# RMII_Ethernet.net
KiCad netlist of a schematic drawn in Altium Designer
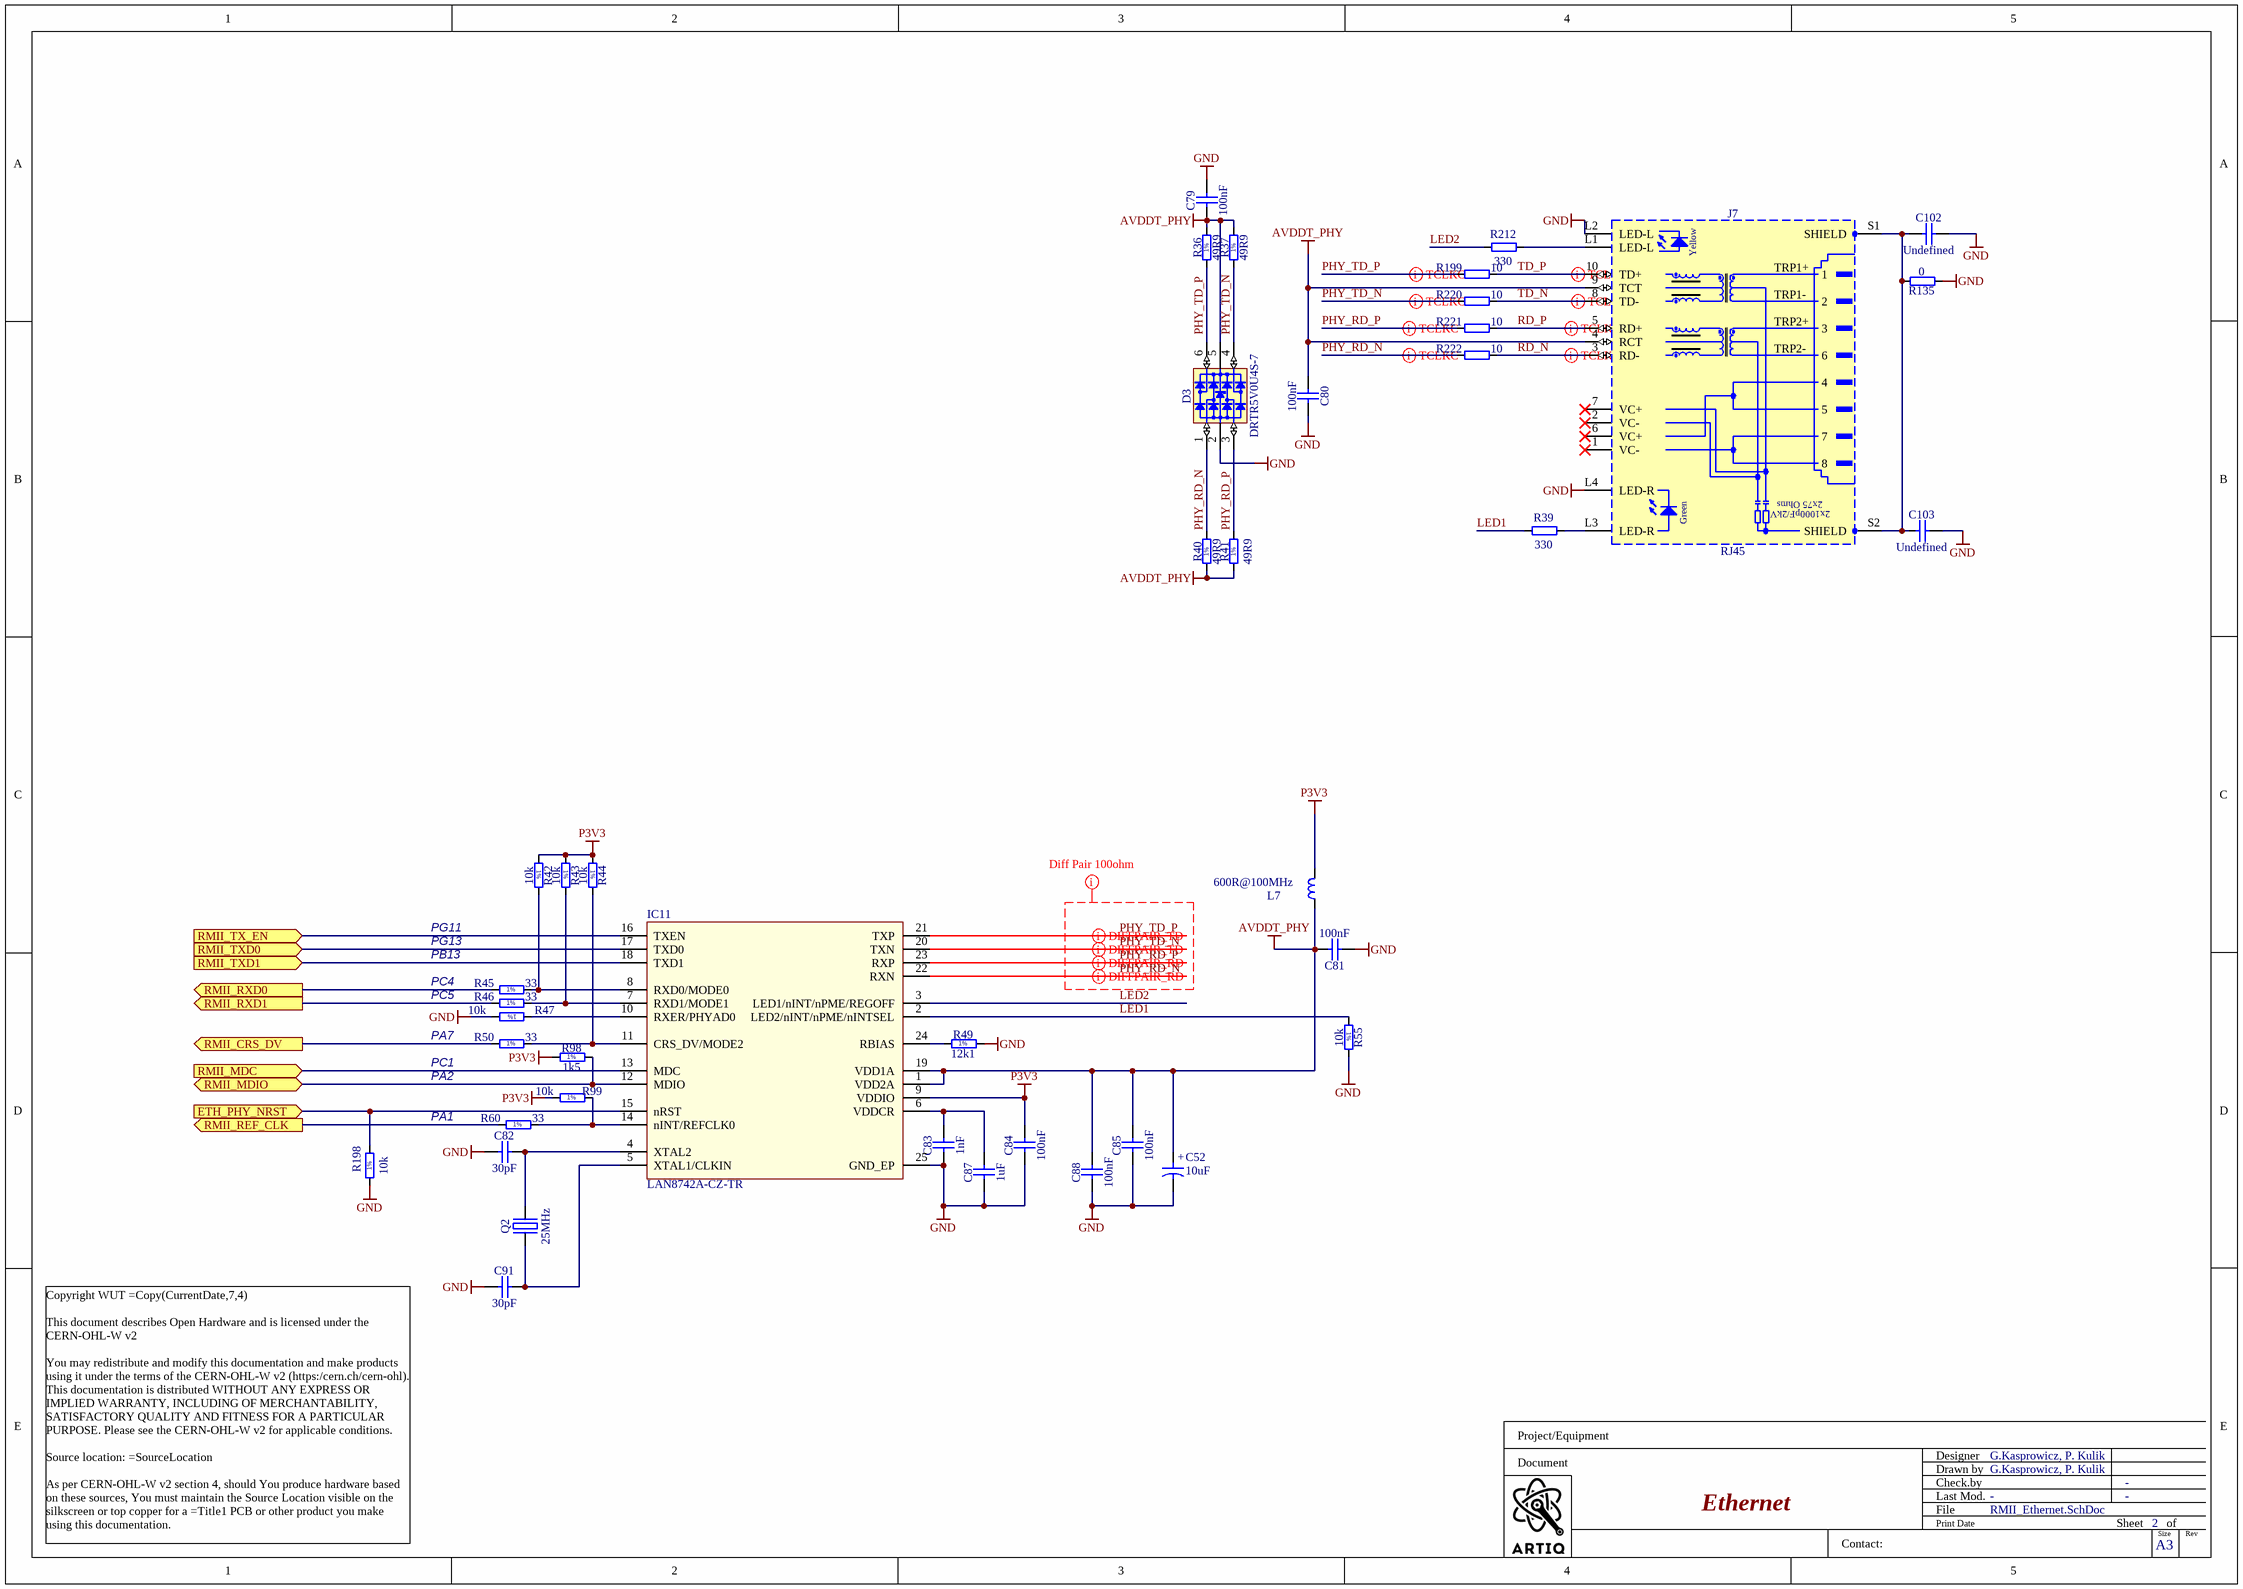
[diagram p0: RMII_Ethernet.SchDoc]

(export (version "E")
  (design (tool "Eeschema 10.0.6"))
  (components
    (comp (ref "C52")
      (value "10uF")
      (footprint "CAPMP3216X180N")
      (description "Polarised capacitor")
      (fields
        (field (name "PART NUMBER") "CTE3216-18_10UF_16V_20%_AVX_TCJ")
        (field (name "VOLTAGE") "16V")
        (field (name "AUTHOR") "CERN DEM JLC")
      )
      (libsource (lib "Capacitors") (part "Capacitor - polarized"))
    )
    (comp (ref "C79")
      (value "100nF")
      (footprint "CAPC1005X55N")
      (description "Non-polarised capacitor")
      (fields
        (field (name "PART NUMBER") "CC0402_100NF_16V_10%_X5R")
        (field (name "VOLTAGE") "16V")
        (field (name "AUTHOR") "CERN DEM JLC")
      )
      (libsource (lib "Capacitors") (part "Capacitor - non polarized"))
    )
    (comp (ref "C80")
      (value "100nF")
      (footprint "CAPC1005X55N")
      (description "Non-polarised capacitor")
      (fields
        (field (name "PART NUMBER") "CC0402_100NF_16V_10%_X5R")
        (field (name "VOLTAGE") "16V")
        (field (name "AUTHOR") "CERN DEM JLC")
      )
      (libsource (lib "Capacitors") (part "Capacitor - non polarized"))
    )
    (comp (ref "C81")
      (value "100nF")
      (footprint "CAPC1005X55N")
      (description "Non-polarised capacitor")
      (fields
        (field (name "PART NUMBER") "CC0402_100NF_16V_10%_X5R")
        (field (name "VOLTAGE") "16V")
        (field (name "AUTHOR") "CERN DEM JLC")
      )
      (libsource (lib "Capacitors") (part "Capacitor - non polarized"))
    )
    (comp (ref "C82")
      (value "30pF")
      (footprint "CAPC1005X55N")
      (description "Non-polarised capacitor")
      (fields
        (field (name "PART NUMBER") "CC0402_30PF_50V_1%_C0G_MURATA_GJM1555C1H300FB01")
        (field (name "VOLTAGE") "50V")
        (field (name "AUTHOR") "CERN DEM BC")
      )
      (libsource (lib "Capacitors") (part "Capacitor - non polarized"))
    )
    (comp (ref "C83")
      (value "1nF")
      (footprint "CAPC1005X55N")
      (description "Non-polarised capacitor")
      (fields
        (field (name "PART NUMBER") "CC0402_1NF_50V_10%_X7R")
        (field (name "VOLTAGE") "50V")
        (field (name "AUTHOR") "CERN DEM JLC")
      )
      (libsource (lib "Capacitors") (part "Capacitor - non polarized"))
    )
    (comp (ref "C84")
      (value "100nF")
      (footprint "CAPC1005X55N")
      (description "Non-polarised capacitor")
      (fields
        (field (name "PART NUMBER") "CC0402_100NF_16V_10%_X5R")
        (field (name "VOLTAGE") "16V")
        (field (name "AUTHOR") "CERN DEM JLC")
      )
      (libsource (lib "Capacitors") (part "Capacitor - non polarized"))
    )
    (comp (ref "C85")
      (value "100nF")
      (footprint "CAPC1005X55N")
      (description "Non-polarised capacitor")
      (fields
        (field (name "PART NUMBER") "CC0402_100NF_16V_10%_X5R")
        (field (name "VOLTAGE") "16V")
        (field (name "AUTHOR") "CERN DEM JLC")
      )
      (libsource (lib "Capacitors") (part "Capacitor - non polarized"))
    )
    (comp (ref "C87")
      (value "1uF")
      (footprint "CAPC1608X87N")
      (description "Non-polarised capacitor")
      (fields
        (field (name "PART NUMBER") "CC0603_1UF_16V_10%_X7R")
        (field (name "VOLTAGE") "16V")
        (field (name "AUTHOR") "CERN DEM JLC")
      )
      (libsource (lib "Capacitors") (part "Capacitor - non polarized"))
    )
    (comp (ref "C88")
      (value "100nF")
      (footprint "CAPC1005X55N")
      (description "Non-polarised capacitor")
      (fields
        (field (name "PART NUMBER") "CC0402_100NF_16V_10%_X5R")
        (field (name "VOLTAGE") "16V")
        (field (name "AUTHOR") "CERN DEM JLC")
      )
      (libsource (lib "Capacitors") (part "Capacitor - non polarized"))
    )
    (comp (ref "C91")
      (value "30pF")
      (footprint "CAPC1005X55N")
      (description "Non-polarised capacitor")
      (fields
        (field (name "PART NUMBER") "CC0402_30PF_50V_1%_C0G_MURATA_GJM1555C1H300FB01")
        (field (name "VOLTAGE") "50V")
        (field (name "AUTHOR") "CERN DEM BC")
      )
      (libsource (lib "Capacitors") (part "Capacitor - non polarized"))
    )
    (comp (ref "C102")
      (value "Undefined")
      (footprint "CAPC2012X135N")
      (description "Non-polarised capacitor")
      (fields (field (name "PART NUMBER") "CC0805_NO-VALUE") (field (name "AUTHOR") "CERN DEM JLC"))
      (libsource (lib "Capacitors") (part "Capacitor - non polarized"))
    )
    (comp (ref "C103")
      (value "Undefined")
      (footprint "CAPC2012X135N")
      (description "Non-polarised capacitor")
      (fields (field (name "PART NUMBER") "CC0805_NO-VALUE") (field (name "AUTHOR") "CERN DEM JLC"))
      (libsource (lib "Capacitors") (part "Capacitor - non polarized"))
    )
    (comp (ref "D3")
      (value "DRTR5V0U4S-7")
      (footprint "SOT65P210X110-6N")
      (description "Integrated Quad Ultra-Low Capacitance ESD Protection")
      (fields (field (name "MANUFACTURER") "DIODES") (field (name "AUTHOR") "GK"))
      (libsource (lib "Diodes") (part "D_TVS_DRTR5V0U4S-7"))
    )
    (comp (ref "IC11")
      (value "LAN8742A-CZ-TR")
      (footprint "QFN24_0R5_4X4")
      (fields (field (name "MANUFACTURER") "MICROCHIP"))
      (libsource (lib "LIBRARY_SCH") (part "IFC_LAN8742A"))
    )
    (comp (ref "J7")
      (value "RJ45")
      (footprint "ABRACON_ARJM11C7-114-BA-EW2")
      (description "MagJack 10/100BaseT, PoE+, 1X1, OG/Y, -40 to 85*C, Tab Up, RoHS")
      (fields
        (field (name "PART NUMBER") "ARJM11C7-114-BA-EW2")
        (field (name "MANUFACTURER") "Abracon")
        (field (name "AUTHOR") "GK")
      )
      (libsource (lib "LIBRARY_SCH") (part "CON_ETH_POE_ARJM11C7"))
    )
    (comp (ref "L7")
      (value "600R@100MHz")
      (footprint "INDC1005X55N")
      (description "Inductor")
      (fields
        (field (name "PART NUMBER") "IND0402_MURATA_BLM15HD601SN1")
        (field (name "POWER") "300mA")
        (field (name "AUTHOR") "CERN DEM JLC")
      )
      (libsource (lib "Inductors & Transformers") (part "Inductor"))
    )
    (comp (ref "Q2")
      (value "25MHz")
      (footprint "XTAL_ABRACON_ABLS")
      (description "Quartz Crystal")
      (fields
        (field (name "PART NUMBER") "XTAL_25MHZ_ABRACON_ABLS-25.000MHZ-B2F-T")
        (field (name "MANUFACTURER") "ABRACON")
        (field (name "AUTHOR") "CERN DEM JLC")
      )
      (libsource (lib "ICs And Semiconductors") (part "Quartz Crystal"))
    )
    (comp (ref "R36")
      (value "49R9")
      (footprint "RESC1005X40N")
      (description "Resistor - 1%")
      (fields
        (field (name "PART NUMBER") "R0402_49R9_1%_0.0625W_100PPM")
        (field (name "POWER") "0.0625W")
        (field (name "AUTHOR") "CERN DEM JLC")
      )
      (libsource (lib "Resistors") (part "Resistor - 1%"))
    )
    (comp (ref "R37")
      (value "49R9")
      (footprint "RESC1005X40N")
      (description "Resistor - 1%")
      (fields
        (field (name "PART NUMBER") "R0402_49R9_1%_0.0625W_100PPM")
        (field (name "POWER") "0.0625W")
        (field (name "AUTHOR") "CERN DEM JLC")
      )
      (libsource (lib "Resistors") (part "Resistor - 1%"))
    )
    (comp (ref "R39")
      (value "330")
      (footprint "RESC1005X40N")
      (description "Resistor - 1%")
      (fields
        (field (name "PART NUMBER") "R0402_330R_1%_0.0625W_100PPM")
        (field (name "POWER") "0.0625W")
        (field (name "AUTHOR") "CERN DEM JLC")
      )
      (libsource (lib "Resistors") (part "Resistor - 1%"))
    )
    (comp (ref "R40")
      (value "49R9")
      (footprint "RESC1005X40N")
      (description "Resistor - 1%")
      (fields
        (field (name "PART NUMBER") "R0402_49R9_1%_0.0625W_100PPM")
        (field (name "POWER") "0.0625W")
        (field (name "AUTHOR") "CERN DEM JLC")
      )
      (libsource (lib "Resistors") (part "Resistor - 1%"))
    )
    (comp (ref "R41")
      (value "49R9")
      (footprint "RESC1005X40N")
      (description "Resistor - 1%")
      (fields
        (field (name "PART NUMBER") "R0402_49R9_1%_0.0625W_100PPM")
        (field (name "POWER") "0.0625W")
        (field (name "AUTHOR") "CERN DEM JLC")
      )
      (libsource (lib "Resistors") (part "Resistor - 1%"))
    )
    (comp (ref "R42")
      (value "10k")
      (footprint "RESC1005X40N")
      (description "Resistor - 1%")
      (fields
        (field (name "PART NUMBER") "R0402_10K_1%_0.0625W_100PPM")
        (field (name "POWER") "0.0625W")
        (field (name "AUTHOR") "CERN DEM JLC")
      )
      (libsource (lib "Resistors") (part "Resistor - 1%"))
    )
    (comp (ref "R43")
      (value "10k")
      (footprint "RESC1005X40N")
      (description "Resistor - 1%")
      (fields
        (field (name "PART NUMBER") "R0402_10K_1%_0.0625W_100PPM")
        (field (name "POWER") "0.0625W")
        (field (name "AUTHOR") "CERN DEM JLC")
      )
      (libsource (lib "Resistors") (part "Resistor - 1%"))
    )
    (comp (ref "R44")
      (value "10k")
      (footprint "RESC1005X40N")
      (description "Resistor - 1%")
      (fields
        (field (name "PART NUMBER") "R0402_10K_1%_0.0625W_100PPM")
        (field (name "POWER") "0.0625W")
        (field (name "AUTHOR") "CERN DEM JLC")
      )
      (libsource (lib "Resistors") (part "Resistor - 1%"))
    )
    (comp (ref "R45")
      (value "33")
      (footprint "RESC1005X40N")
      (description "Resistor - 1%")
      (fields
        (field (name "PART NUMBER") "R0402_33R_1%_0.0625W_100PPM")
        (field (name "POWER") "0.0625W")
        (field (name "AUTHOR") "CERN DEM JLC")
      )
      (libsource (lib "Resistors") (part "Resistor - 1%"))
    )
    (comp (ref "R46")
      (value "33")
      (footprint "RESC1005X40N")
      (description "Resistor - 1%")
      (fields
        (field (name "PART NUMBER") "R0402_33R_1%_0.0625W_100PPM")
        (field (name "POWER") "0.0625W")
        (field (name "AUTHOR") "CERN DEM JLC")
      )
      (libsource (lib "Resistors") (part "Resistor - 1%"))
    )
    (comp (ref "R47")
      (value "10k")
      (footprint "RESC1005X40N")
      (description "Resistor - 1%")
      (fields
        (field (name "PART NUMBER") "R0402_10K_1%_0.0625W_100PPM")
        (field (name "POWER") "0.0625W")
        (field (name "AUTHOR") "CERN DEM JLC")
      )
      (libsource (lib "Resistors") (part "Resistor - 1%"))
    )
    (comp (ref "R49")
      (value "12k1")
      (footprint "RESC1005X40N")
      (description "Resistor - 1%")
      (fields
        (field (name "PART NUMBER") "R0402_12K1_1%_0.0625W_100PPM")
        (field (name "POWER") "0.0625W")
        (field (name "AUTHOR") "CERN DEM JLC")
      )
      (libsource (lib "Resistors") (part "Resistor - 1%"))
    )
    (comp (ref "R50")
      (value "33")
      (footprint "RESC1005X40N")
      (description "Resistor - 1%")
      (fields
        (field (name "PART NUMBER") "R0402_33R_1%_0.0625W_100PPM")
        (field (name "POWER") "0.0625W")
        (field (name "AUTHOR") "CERN DEM JLC")
      )
      (libsource (lib "Resistors") (part "Resistor - 1%"))
    )
    (comp (ref "R55")
      (value "10k")
      (footprint "RESC1005X40N")
      (description "Resistor - 1%")
      (fields
        (field (name "PART NUMBER") "R0402_10K_1%_0.0625W_100PPM")
        (field (name "POWER") "0.0625W")
        (field (name "AUTHOR") "CERN DEM JLC")
      )
      (libsource (lib "Resistors") (part "Resistor - 1%"))
    )
    (comp (ref "R60")
      (value "33")
      (footprint "RESC1005X40N")
      (description "Resistor - 1%")
      (fields
        (field (name "PART NUMBER") "R0402_33R_1%_0.0625W_100PPM")
        (field (name "POWER") "0.0625W")
        (field (name "AUTHOR") "CERN DEM JLC")
      )
      (libsource (lib "Resistors") (part "Resistor - 1%"))
    )
    (comp (ref "R98")
      (value "1k5")
      (footprint "RESC1005X40N")
      (description "Resistor - 1%")
      (fields
        (field (name "PART NUMBER") "R0402_1K5_1%_0.0625W_100PPM")
        (field (name "POWER") "0.0625W")
        (field (name "AUTHOR") "CERN DEM JLC")
      )
      (libsource (lib "Resistors") (part "Resistor - 1%"))
    )
    (comp (ref "R99")
      (value "10k")
      (footprint "RESC1005X40N")
      (description "Resistor - 1%")
      (fields
        (field (name "PART NUMBER") "R0402_10K_1%_0.0625W_100PPM")
        (field (name "POWER") "0.0625W")
        (field (name "AUTHOR") "CERN DEM JLC")
      )
      (libsource (lib "Resistors") (part "Resistor - 1%"))
    )
    (comp (ref "R135")
      (value "0")
      (footprint "RESC1608X55N")
      (description "Resistor")
      (fields
        (field (name "PART NUMBER") "R0603_0R_JUMPER")
        (field (name "MANUFACTURER") "GENERIC")
        (field (name "AUTHOR") "CERN DEM JLC")
      )
      (libsource (lib "Resistors") (part "Resistor"))
    )
    (comp (ref "R198")
      (value "10k")
      (footprint "RESC1005X40N")
      (description "Resistor - 1%")
      (fields
        (field (name "PART NUMBER") "R0402_10K_1%_0.0625W_100PPM")
        (field (name "POWER") "0.0625W")
        (field (name "AUTHOR") "CERN DEM JLC")
      )
      (libsource (lib "Resistors") (part "Resistor - 1%"))
    )
    (comp (ref "R199")
      (value "10")
      (footprint "RESC1005X40N")
      (description "Resistor - 1%")
      (fields
        (field (name "PART NUMBER") "R0402_10R_1%_0.0625W_200PPM")
        (field (name "POWER") "0.0625W")
        (field (name "AUTHOR") "CERN DEM JLC")
      )
      (libsource (lib "Resistors") (part "Resistor - 1%"))
    )
    (comp (ref "R212")
      (value "330")
      (footprint "RESC1005X40N")
      (description "Resistor - 1%")
      (fields
        (field (name "PART NUMBER") "R0402_330R_1%_0.0625W_100PPM")
        (field (name "POWER") "0.0625W")
        (field (name "AUTHOR") "CERN DEM JLC")
      )
      (libsource (lib "Resistors") (part "Resistor - 1%"))
    )
    (comp (ref "R220")
      (value "10")
      (footprint "RESC1005X40N")
      (description "Resistor - 1%")
      (fields
        (field (name "PART NUMBER") "R0402_10R_1%_0.0625W_200PPM")
        (field (name "POWER") "0.0625W")
        (field (name "AUTHOR") "CERN DEM JLC")
      )
      (libsource (lib "Resistors") (part "Resistor - 1%"))
    )
    (comp (ref "R221")
      (value "10")
      (footprint "RESC1005X40N")
      (description "Resistor - 1%")
      (fields
        (field (name "PART NUMBER") "R0402_10R_1%_0.0625W_200PPM")
        (field (name "POWER") "0.0625W")
        (field (name "AUTHOR") "CERN DEM JLC")
      )
      (libsource (lib "Resistors") (part "Resistor - 1%"))
    )
    (comp (ref "R222")
      (value "10")
      (footprint "RESC1005X40N")
      (description "Resistor - 1%")
      (fields
        (field (name "PART NUMBER") "R0402_10R_1%_0.0625W_200PPM")
        (field (name "POWER") "0.0625W")
        (field (name "AUTHOR") "CERN DEM JLC")
      )
      (libsource (lib "Resistors") (part "Resistor - 1%"))
    )
  )
  (nets
    (net (code "1") (name "/ETH_PHY_NRST") (class "Default")
      (node (ref "IC11") (pin "15") (pinfunction "nRST_15") (pintype "passive"))
      (node (ref "R198") (pin "2") (pinfunction "2_2") (pintype "passive"))
    )
    (net (code "2") (name "/LED1") (class "Default")
      (node (ref "IC11") (pin "2") (pinfunction "LED2/nINT/nPME/nINTSEL_2") (pintype "passive"))
      (node (ref "R39") (pin "1") (pinfunction "1_1") (pintype "passive"))
      (node (ref "R55") (pin "1") (pinfunction "1_1") (pintype "passive"))
    )
    (net (code "3") (name "/LED2") (class "Default")
      (node (ref "IC11") (pin "3") (pinfunction "LED1/nINT/nPME/REGOFF_3") (pintype "passive"))
      (node (ref "R212") (pin "1") (pinfunction "1_1") (pintype "passive"))
    )
    (net (code "4") (name "/PHY_RD_N") (class "Default")
      (node (ref "D3") (pin "1") (pinfunction "I/O1_1") (pintype "bidirectional"))
      (node (ref "IC11") (pin "22") (pinfunction "RXN_22") (pintype "passive"))
      (node (ref "R222") (pin "1") (pinfunction "1_1") (pintype "passive"))
      (node (ref "R40") (pin "2") (pinfunction "2_2") (pintype "passive"))
    )
    (net (code "5") (name "/PHY_RD_P") (class "Default")
      (node (ref "D3") (pin "3") (pinfunction "I/O2_3") (pintype "bidirectional"))
      (node (ref "IC11") (pin "23") (pinfunction "RXP_23") (pintype "passive"))
      (node (ref "R221") (pin "1") (pinfunction "1_1") (pintype "passive"))
      (node (ref "R41") (pin "2") (pinfunction "2_2") (pintype "passive"))
    )
    (net (code "6") (name "/PHY_TD_N") (class "Default")
      (node (ref "D3") (pin "4") (pinfunction "I/O3_4") (pintype "bidirectional"))
      (node (ref "IC11") (pin "20") (pinfunction "TXN_20") (pintype "passive"))
      (node (ref "R220") (pin "1") (pinfunction "1_1") (pintype "passive"))
      (node (ref "R37") (pin "1") (pinfunction "1_1") (pintype "passive"))
    )
    (net (code "7") (name "/PHY_TD_P") (class "Default")
      (node (ref "D3") (pin "6") (pinfunction "I/O4_6") (pintype "bidirectional"))
      (node (ref "IC11") (pin "21") (pinfunction "TXP_21") (pintype "passive"))
      (node (ref "R199") (pin "1") (pinfunction "1_1") (pintype "passive"))
      (node (ref "R36") (pin "1") (pinfunction "1_1") (pintype "passive"))
    )
    (net (code "8") (name "/RD_N") (class "Default")
      (node (ref "J7") (pin "3") (pinfunction "RD-_3") (pintype "bidirectional"))
      (node (ref "R222") (pin "2") (pinfunction "2_2") (pintype "passive"))
    )
    (net (code "9") (name "/RD_P") (class "Default")
      (node (ref "J7") (pin "5") (pinfunction "RD+_5") (pintype "bidirectional"))
      (node (ref "R221") (pin "2") (pinfunction "2_2") (pintype "passive"))
    )
    (net (code "10") (name "/RMII_CRS_DV") (class "Default")
      (node (ref "R50") (pin "1") (pinfunction "1_1") (pintype "passive"))
    )
    (net (code "11") (name "/RMII_MDC") (class "Default")
      (node (ref "IC11") (pin "13") (pinfunction "MDC_13") (pintype "passive"))
    )
    (net (code "12") (name "/RMII_MDIO") (class "Default")
      (node (ref "IC11") (pin "12") (pinfunction "MDIO_12") (pintype "passive"))
      (node (ref "R98") (pin "2") (pinfunction "2_2") (pintype "passive"))
    )
    (net (code "13") (name "/RMII_REF_CLK") (class "Default")
      (node (ref "R60") (pin "1") (pinfunction "1_1") (pintype "passive"))
    )
    (net (code "14") (name "/RMII_RXD0") (class "Default")
      (node (ref "R45") (pin "1") (pinfunction "1_1") (pintype "passive"))
    )
    (net (code "15") (name "/RMII_RXD1") (class "Default")
      (node (ref "R46") (pin "1") (pinfunction "1_1") (pintype "passive"))
    )
    (net (code "16") (name "/RMII_TXD0") (class "Default")
      (node (ref "IC11") (pin "17") (pinfunction "TXD0_17") (pintype "passive"))
    )
    (net (code "17") (name "/RMII_TXD1") (class "Default")
      (node (ref "IC11") (pin "18") (pinfunction "TXD1_18") (pintype "passive"))
    )
    (net (code "18") (name "/RMII_TX_EN") (class "Default")
      (node (ref "IC11") (pin "16") (pinfunction "TXEN_16") (pintype "passive"))
    )
    (net (code "19") (name "/TD_N") (class "Default")
      (node (ref "J7") (pin "8") (pinfunction "TD-_8") (pintype "bidirectional"))
      (node (ref "R220") (pin "2") (pinfunction "2_2") (pintype "passive"))
    )
    (net (code "20") (name "/TD_P") (class "Default")
      (node (ref "J7") (pin "10") (pinfunction "TD+_10") (pintype "bidirectional"))
      (node (ref "R199") (pin "2") (pinfunction "2_2") (pintype "passive"))
    )
    (net (code "21") (name "AVDDT_PHY") (class "Default")
      (node (ref "C52") (pin "1") (pinfunction "1_1") (pintype "passive"))
      (node (ref "C79") (pin "1") (pinfunction "1_1") (pintype "passive"))
      (node (ref "C80") (pin "2") (pinfunction "2_2") (pintype "passive"))
      (node (ref "C81") (pin "2") (pinfunction "2_2") (pintype "passive"))
      (node (ref "C85") (pin "2") (pinfunction "2_2") (pintype "passive"))
      (node (ref "C88") (pin "2") (pinfunction "2_2") (pintype "passive"))
      (node (ref "D3") (pin "5") (pinfunction "VBUS_5") (pintype "power_in"))
      (node (ref "IC11") (pin "1") (pinfunction "VDD2A_1") (pintype "passive"))
      (node (ref "IC11") (pin "19") (pinfunction "VDD1A_19") (pintype "passive"))
      (node (ref "J7") (pin "4") (pinfunction "RCT_4") (pintype "bidirectional"))
      (node (ref "J7") (pin "9") (pinfunction "TCT_9") (pintype "bidirectional"))
      (node (ref "L7") (pin "1") (pinfunction "1_1") (pintype "passive"))
      (node (ref "R36") (pin "2") (pinfunction "2_2") (pintype "passive"))
      (node (ref "R37") (pin "2") (pinfunction "2_2") (pintype "passive"))
      (node (ref "R40") (pin "1") (pinfunction "1_1") (pintype "passive"))
      (node (ref "R41") (pin "1") (pinfunction "1_1") (pintype "passive"))
    )
    (net (code "22") (name "GND") (class "Default")
      (node (ref "C102") (pin "2") (pinfunction "2_2") (pintype "passive"))
      (node (ref "C103") (pin "2") (pinfunction "2_2") (pintype "passive"))
      (node (ref "C52") (pin "2") (pinfunction "2_2") (pintype "passive"))
      (node (ref "C79") (pin "2") (pinfunction "2_2") (pintype "passive"))
      (node (ref "C80") (pin "1") (pinfunction "1_1") (pintype "passive"))
      (node (ref "C81") (pin "1") (pinfunction "1_1") (pintype "passive"))
      (node (ref "C82") (pin "1") (pinfunction "1_1") (pintype "passive"))
      (node (ref "C83") (pin "1") (pinfunction "1_1") (pintype "passive"))
      (node (ref "C84") (pin "1") (pinfunction "1_1") (pintype "passive"))
      (node (ref "C85") (pin "1") (pinfunction "1_1") (pintype "passive"))
      (node (ref "C87") (pin "1") (pinfunction "1_1") (pintype "passive"))
      (node (ref "C88") (pin "1") (pinfunction "1_1") (pintype "passive"))
      (node (ref "C91") (pin "1") (pinfunction "1_1") (pintype "passive"))
      (node (ref "D3") (pin "2") (pinfunction "GND_2") (pintype "power_in"))
      (node (ref "IC11") (pin "25") (pinfunction "GND_EP_25") (pintype "passive"))
      (node (ref "J7") (pin "L2") (pinfunction "LED-L_L2") (pintype "passive"))
      (node (ref "J7") (pin "L4") (pinfunction "LED-R_L4") (pintype "passive"))
      (node (ref "R135") (pin "1") (pinfunction "1_1") (pintype "passive"))
      (node (ref "R198") (pin "1") (pinfunction "1_1") (pintype "passive"))
      (node (ref "R47") (pin "2") (pinfunction "2_2") (pintype "passive"))
      (node (ref "R49") (pin "2") (pinfunction "2_2") (pintype "passive"))
      (node (ref "R55") (pin "2") (pinfunction "2_2") (pintype "passive"))
    )
    (net (code "23") (name "Net-(C102-Pad1)") (class "Default")
      (node (ref "C102") (pin "1") (pinfunction "1_1") (pintype "passive"))
      (node (ref "C103") (pin "1") (pinfunction "1_1") (pintype "passive"))
      (node (ref "J7") (pin "S1") (pinfunction "SHIELD_S1") (pintype "power_in"))
      (node (ref "J7") (pin "S2") (pinfunction "SHIELD_S2") (pintype "power_in"))
      (node (ref "R135") (pin "2") (pinfunction "2_2") (pintype "passive"))
    )
    (net (code "24") (name "Net-(IC11-CRS_DV{slash}MODE2)") (class "Default")
      (node (ref "IC11") (pin "11") (pinfunction "CRS_DV/MODE2_11") (pintype "passive"))
      (node (ref "R44") (pin "2") (pinfunction "2_2") (pintype "passive"))
      (node (ref "R50") (pin "2") (pinfunction "2_2") (pintype "passive"))
    )
    (net (code "25") (name "Net-(IC11-RBIAS)") (class "Default")
      (node (ref "IC11") (pin "24") (pinfunction "RBIAS_24") (pintype "passive"))
      (node (ref "R49") (pin "1") (pinfunction "1_1") (pintype "passive"))
    )
    (net (code "26") (name "Net-(IC11-RXD0{slash}MODE0)") (class "Default")
      (node (ref "IC11") (pin "8") (pinfunction "RXD0/MODE0_8") (pintype "passive"))
      (node (ref "R42") (pin "2") (pinfunction "2_2") (pintype "passive"))
      (node (ref "R45") (pin "2") (pinfunction "2_2") (pintype "passive"))
    )
    (net (code "27") (name "Net-(IC11-RXD1{slash}MODE1)") (class "Default")
      (node (ref "IC11") (pin "7") (pinfunction "RXD1/MODE1_7") (pintype "passive"))
      (node (ref "R43") (pin "2") (pinfunction "2_2") (pintype "passive"))
      (node (ref "R46") (pin "2") (pinfunction "2_2") (pintype "passive"))
    )
    (net (code "28") (name "Net-(IC11-RXER{slash}PHYAD0)") (class "Default")
      (node (ref "IC11") (pin "10") (pinfunction "RXER/PHYAD0_10") (pintype "passive"))
      (node (ref "R47") (pin "1") (pinfunction "1_1") (pintype "passive"))
    )
    (net (code "29") (name "Net-(IC11-VDDCR)") (class "Default")
      (node (ref "C83") (pin "2") (pinfunction "2_2") (pintype "passive"))
      (node (ref "C87") (pin "2") (pinfunction "2_2") (pintype "passive"))
      (node (ref "IC11") (pin "6") (pinfunction "VDDCR_6") (pintype "passive"))
    )
    (net (code "30") (name "Net-(IC11-XTAL1{slash}CLKIN)") (class "Default")
      (node (ref "C91") (pin "2") (pinfunction "2_2") (pintype "passive"))
      (node (ref "IC11") (pin "5") (pinfunction "XTAL1/CLKIN_5") (pintype "passive"))
      (node (ref "Q2") (pin "1") (pinfunction "OSC1_1") (pintype "passive"))
    )
    (net (code "31") (name "Net-(IC11-XTAL2)") (class "Default")
      (node (ref "C82") (pin "2") (pinfunction "2_2") (pintype "passive"))
      (node (ref "IC11") (pin "4") (pinfunction "XTAL2_4") (pintype "passive"))
      (node (ref "Q2") (pin "2") (pinfunction "OSC2_2") (pintype "passive"))
    )
    (net (code "32") (name "Net-(IC11-nINT{slash}REFCLK0)") (class "Default")
      (node (ref "IC11") (pin "14") (pinfunction "nINT/REFCLK0_14") (pintype "passive"))
      (node (ref "R60") (pin "2") (pinfunction "2_2") (pintype "passive"))
      (node (ref "R99") (pin "2") (pinfunction "2_2") (pintype "passive"))
    )
    (net (code "33") (name "Net-(J7-LED-L-PadL1)") (class "Default")
      (node (ref "J7") (pin "L1") (pinfunction "LED-L_L1") (pintype "passive"))
      (node (ref "R212") (pin "2") (pinfunction "2_2") (pintype "passive"))
    )
    (net (code "34") (name "Net-(J7-LED-R-PadL3)") (class "Default")
      (node (ref "J7") (pin "L3") (pinfunction "LED-R_L3") (pintype "passive"))
      (node (ref "R39") (pin "2") (pinfunction "2_2") (pintype "passive"))
    )
    (net (code "35") (name "P3V3") (class "Default")
      (node (ref "C84") (pin "2") (pinfunction "2_2") (pintype "passive"))
      (node (ref "IC11") (pin "9") (pinfunction "VDDIO_9") (pintype "passive"))
      (node (ref "L7") (pin "2") (pinfunction "2_2") (pintype "passive"))
      (node (ref "R42") (pin "1") (pinfunction "1_1") (pintype "passive"))
      (node (ref "R43") (pin "1") (pinfunction "1_1") (pintype "passive"))
      (node (ref "R44") (pin "1") (pinfunction "1_1") (pintype "passive"))
      (node (ref "R98") (pin "1") (pinfunction "1_1") (pintype "passive"))
      (node (ref "R99") (pin "1") (pinfunction "1_1") (pintype "passive"))
    )
    (net (code "36") (name "unconnected-(J7-VC+-Pad6)") (class "Default")
      (node (ref "J7") (pin "6") (pinfunction "VC+_6") (pintype "passive+no_connect"))
    )
    (net (code "37") (name "unconnected-(J7-VC+-Pad7)") (class "Default")
      (node (ref "J7") (pin "7") (pinfunction "VC+_7") (pintype "passive+no_connect"))
    )
    (net (code "38") (name "unconnected-(J7-VC--Pad1)") (class "Default")
      (node (ref "J7") (pin "1") (pinfunction "VC-_1") (pintype "passive+no_connect"))
    )
    (net (code "39") (name "unconnected-(J7-VC--Pad2)") (class "Default")
      (node (ref "J7") (pin "2") (pinfunction "VC-_2") (pintype "passive+no_connect"))
    )
  )
)
